# Top_board.net
KiCad netlist of a schematic drawn in Altium Designer
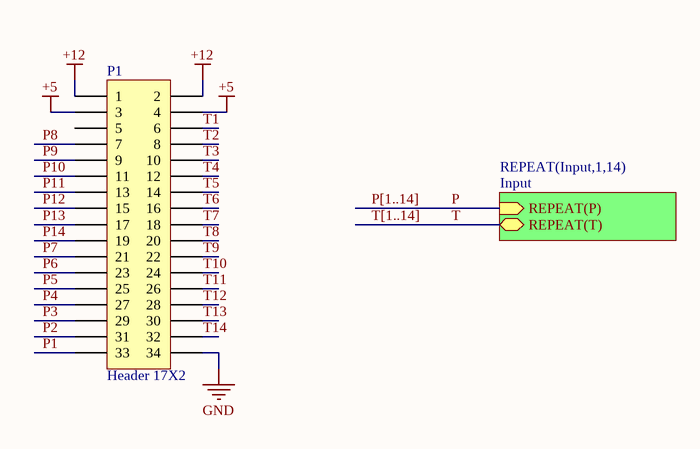
[diagram p0: Top_board.SchDoc]

(export (version "E")
  (design (tool "Eeschema 10.0.6"))
  (components
    (comp (ref "P1")
      (value "Header 17X2")
      (footprint "HDR2X17-PLC")
      (description "Header, 17-Pin, Dual row")
      (fields (field (name "PUBLISHER") "Altium Limited"))
      (libsource (lib "altium-import") (part "root_0_Header 17X2_"))
    )
  )
  (nets
    (net (code "1") (name "+5") (class "Default")
      (node (ref "P1") (pin "3") (pinfunction "3_3") (pintype "passive"))
      (node (ref "P1") (pin "4") (pinfunction "4_4") (pintype "passive"))
    )
    (net (code "2") (name "+12") (class "Default")
      (node (ref "P1") (pin "1") (pinfunction "1_1") (pintype "passive"))
      (node (ref "P1") (pin "2") (pinfunction "2_2") (pintype "passive"))
    )
    (net (code "4") (name "/P1") (class "Default")
      (node (ref "P1") (pin "33") (pinfunction "33_33") (pintype "passive"))
    )
    (net (code "5") (name "/P2") (class "Default")
      (node (ref "P1") (pin "31") (pinfunction "31_31") (pintype "passive"))
    )
    (net (code "6") (name "/P3") (class "Default")
      (node (ref "P1") (pin "29") (pinfunction "29_29") (pintype "passive"))
    )
    (net (code "7") (name "/P4") (class "Default")
      (node (ref "P1") (pin "27") (pinfunction "27_27") (pintype "passive"))
    )
    (net (code "8") (name "/P5") (class "Default")
      (node (ref "P1") (pin "25") (pinfunction "25_25") (pintype "passive"))
    )
    (net (code "9") (name "/P6") (class "Default")
      (node (ref "P1") (pin "23") (pinfunction "23_23") (pintype "passive"))
    )
    (net (code "10") (name "/P7") (class "Default")
      (node (ref "P1") (pin "21") (pinfunction "21_21") (pintype "passive"))
    )
    (net (code "11") (name "/P8") (class "Default")
      (node (ref "P1") (pin "7") (pinfunction "7_7") (pintype "passive"))
    )
    (net (code "12") (name "/P9") (class "Default")
      (node (ref "P1") (pin "9") (pinfunction "9_9") (pintype "passive"))
    )
    (net (code "13") (name "/P10") (class "Default")
      (node (ref "P1") (pin "11") (pinfunction "11_11") (pintype "passive"))
    )
    (net (code "14") (name "/P11") (class "Default")
      (node (ref "P1") (pin "13") (pinfunction "13_13") (pintype "passive"))
    )
    (net (code "15") (name "/P12") (class "Default")
      (node (ref "P1") (pin "15") (pinfunction "15_15") (pintype "passive"))
    )
    (net (code "16") (name "/P13") (class "Default")
      (node (ref "P1") (pin "17") (pinfunction "17_17") (pintype "passive"))
    )
    (net (code "17") (name "/P14") (class "Default")
      (node (ref "P1") (pin "19") (pinfunction "19_19") (pintype "passive"))
    )
    (net (code "20") (name "/T1") (class "Default")
      (node (ref "P1") (pin "6") (pinfunction "6_6") (pintype "passive"))
    )
    (net (code "21") (name "/T2") (class "Default")
      (node (ref "P1") (pin "8") (pinfunction "8_8") (pintype "passive"))
    )
    (net (code "22") (name "/T3") (class "Default")
      (node (ref "P1") (pin "10") (pinfunction "10_10") (pintype "passive"))
    )
    (net (code "23") (name "/T4") (class "Default")
      (node (ref "P1") (pin "12") (pinfunction "12_12") (pintype "passive"))
    )
    (net (code "24") (name "/T5") (class "Default")
      (node (ref "P1") (pin "14") (pinfunction "14_14") (pintype "passive"))
    )
    (net (code "25") (name "/T6") (class "Default")
      (node (ref "P1") (pin "16") (pinfunction "16_16") (pintype "passive"))
    )
    (net (code "26") (name "/T7") (class "Default")
      (node (ref "P1") (pin "18") (pinfunction "18_18") (pintype "passive"))
    )
    (net (code "27") (name "/T8") (class "Default")
      (node (ref "P1") (pin "20") (pinfunction "20_20") (pintype "passive"))
    )
    (net (code "28") (name "/T9") (class "Default")
      (node (ref "P1") (pin "22") (pinfunction "22_22") (pintype "passive"))
    )
    (net (code "29") (name "/T10") (class "Default")
      (node (ref "P1") (pin "24") (pinfunction "24_24") (pintype "passive"))
    )
    (net (code "30") (name "/T11") (class "Default")
      (node (ref "P1") (pin "26") (pinfunction "26_26") (pintype "passive"))
    )
    (net (code "31") (name "/T12") (class "Default")
      (node (ref "P1") (pin "28") (pinfunction "28_28") (pintype "passive"))
    )
    (net (code "32") (name "/T13") (class "Default")
      (node (ref "P1") (pin "30") (pinfunction "30_30") (pintype "passive"))
    )
    (net (code "33") (name "/T14") (class "Default")
      (node (ref "P1") (pin "32") (pinfunction "32_32") (pintype "passive"))
    )
    (net (code "35") (name "GND") (class "Default")
      (node (ref "P1") (pin "34") (pinfunction "34_34") (pintype "passive"))
    )
    (net (code "36") (name "unconnected-(P1-Pad5)") (class "Default")
      (node (ref "P1") (pin "5") (pinfunction "5_5") (pintype "passive"))
    )
  )
)
